# Regulador_RS232.net
KiCad netlist of a schematic drawn in EAGLE
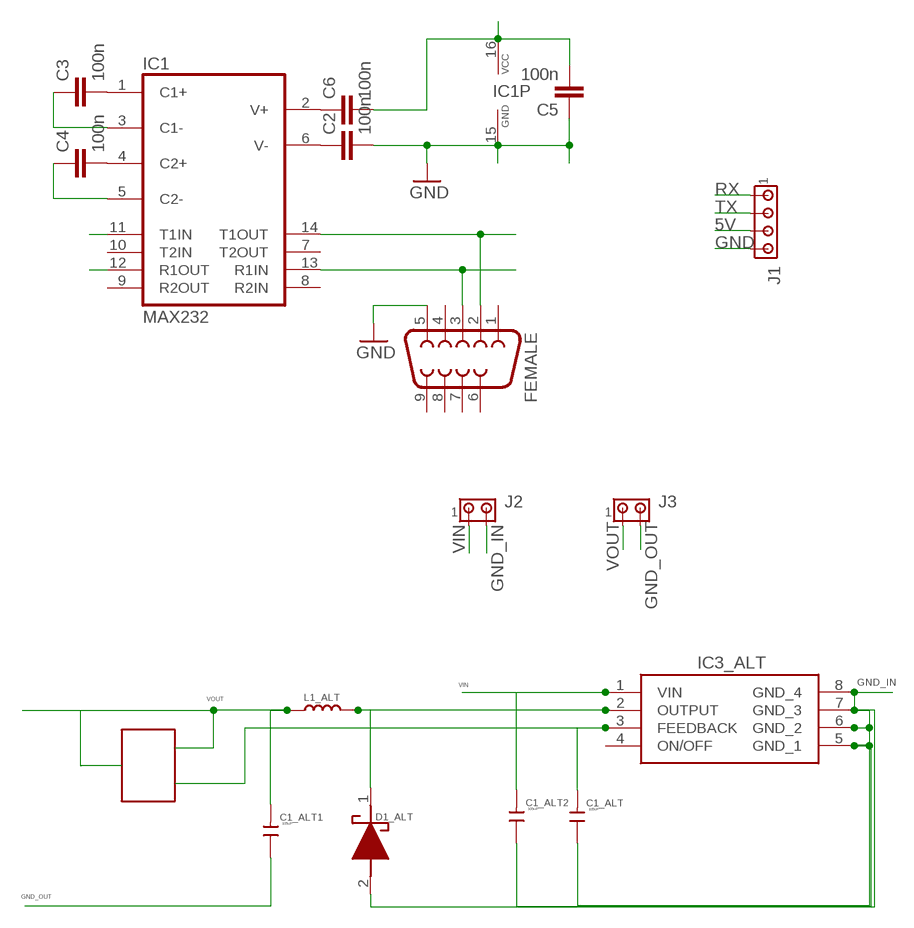
[diagram p0: schematic, sheet 1]

(export (version "E")
  (design (tool "Eeschema 10.0.6"))
  (components
    (comp (ref "C1_ALT")
      (value "105uF")
      (footprint "eagle-import:C0805")
      (libsource (lib "eagle-import") (part "C-0805"))
    )
    (comp (ref "C1_ALT1")
      (value "105uF")
      (footprint "eagle-import:C0805")
      (libsource (lib "eagle-import") (part "C-0805"))
    )
    (comp (ref "C1_ALT2")
      (value "105uF")
      (footprint "eagle-import:C0805")
      (libsource (lib "eagle-import") (part "C-0805"))
    )
    (comp (ref "C2")
      (value "100n")
      (footprint "eagle-import:C0805")
      (libsource (lib "eagle-import") (part "C-EUC0805"))
    )
    (comp (ref "C3")
      (value "100n")
      (footprint "eagle-import:C0805")
      (libsource (lib "eagle-import") (part "C-EUC0805"))
    )
    (comp (ref "C4")
      (value "100n")
      (footprint "eagle-import:C0805")
      (libsource (lib "eagle-import") (part "C-EUC0805"))
    )
    (comp (ref "C5")
      (value "100n")
      (footprint "eagle-import:C0805")
      (libsource (lib "eagle-import") (part "C-EUC0805"))
    )
    (comp (ref "C6")
      (value "100n")
      (footprint "eagle-import:C0805")
      (libsource (lib "eagle-import") (part "C-EUC0805"))
    )
    (comp (ref "D1_ALT")
      (value "1N5819HW1-7-F")
      (footprint "eagle-import:SODFL3518X115N")
      (fields (field (name "MOUSER_PART_NUMBER") "621-1N5819HW1-7-F"))
      (libsource (lib "eagle-import") (part "1N5819HW1-7-F"))
    )
    (comp (ref "FEMALE")
      (value "F09H")
      (footprint "eagle-import:F09H")
      (libsource (lib "eagle-import") (part "F09H"))
    )
    (comp (ref "IC1")
      (value "MAX232")
      (footprint "eagle-import:SO16")
      (libsource (lib "eagle-import") (part "MAX232ECWES"))
    )
    (comp (ref "IC3_ALT")
      (value "XL1509-3.3E1")
      (footprint "eagle-import:SOIC127P600X175-8N")
      (libsource (lib "eagle-import") (part "XL1509-3.3E1"))
    )
    (comp (ref "J1")
      (value "MTA04-156")
      (footprint "eagle-import:1X4MTA")
      (libsource (lib "eagle-import") (part "MTA04-156"))
    )
    (comp (ref "J2")
      (value "MTA02-156")
      (footprint "eagle-import:1X2MTA")
      (libsource (lib "eagle-import") (part "MTA02-156"))
    )
    (comp (ref "J3")
      (value "MTA02-156")
      (footprint "eagle-import:1X2MTA")
      (libsource (lib "eagle-import") (part "MTA02-156"))
    )
    (comp (ref "L1_ALT")
      (value "47uH")
      (footprint "eagle-import:PIO73")
      (libsource (lib "eagle-import") (part "L'PIO73'"))
    )
    (comp (ref "U$1")
      (value "TRIMPOT")
      (footprint "eagle-import:TRIMPOT")
      (libsource (lib "eagle-import") (part "TRIMPOT"))
    )
  )
  (nets
    (net (code "1") (name "/5V") (class "Default")
      (node (ref "C5") (pin "2") (pinfunction "2_2") (pintype "passive"))
      (node (ref "C6") (pin "2") (pinfunction "2_2") (pintype "passive"))
      (node (ref "IC1") (pin "16") (pinfunction "VCC_16") (pintype "power_in"))
      (node (ref "J1") (pin "3") (pinfunction "3_3") (pintype "passive"))
    )
    (net (code "2") (name "/GND_IN") (class "Default")
      (node (ref "C1_ALT") (pin "1") (pinfunction "1_1") (pintype "passive"))
      (node (ref "C1_ALT2") (pin "1") (pinfunction "1_1") (pintype "passive"))
      (node (ref "D1_ALT") (pin "2") (pinfunction "A_2") (pintype "bidirectional"))
      (node (ref "IC3_ALT") (pin "5") (pinfunction "GND_1_5") (pintype "bidirectional"))
      (node (ref "IC3_ALT") (pin "6") (pinfunction "GND_2_6") (pintype "bidirectional"))
      (node (ref "IC3_ALT") (pin "7") (pinfunction "GND_3_7") (pintype "bidirectional"))
      (node (ref "IC3_ALT") (pin "8") (pinfunction "GND_4_8") (pintype "bidirectional"))
      (node (ref "J2") (pin "2") (pinfunction "2_2") (pintype "passive"))
    )
    (net (code "3") (name "/GND_OUT") (class "Default")
      (node (ref "C1_ALT1") (pin "1") (pinfunction "1_1") (pintype "passive"))
      (node (ref "J3") (pin "2") (pinfunction "2_2") (pintype "passive"))
    )
    (net (code "4") (name "/RX") (class "Default")
      (node (ref "IC1") (pin "12") (pinfunction "R1OUT_12") (pintype "output"))
      (node (ref "J1") (pin "1") (pinfunction "1_1") (pintype "passive"))
    )
    (net (code "5") (name "/TX") (class "Default")
      (node (ref "IC1") (pin "11") (pinfunction "T1IN_11") (pintype "input"))
      (node (ref "J1") (pin "2") (pinfunction "2_2") (pintype "passive"))
    )
    (net (code "6") (name "/VIN") (class "Default")
      (node (ref "C1_ALT2") (pin "2") (pinfunction "2_2") (pintype "passive"))
      (node (ref "IC3_ALT") (pin "1") (pinfunction "VIN_1") (pintype "bidirectional"))
      (node (ref "J2") (pin "1") (pinfunction "1_1") (pintype "passive"))
    )
    (net (code "7") (name "/VOUT") (class "Default")
      (node (ref "C1_ALT1") (pin "2") (pinfunction "2_2") (pintype "passive"))
      (node (ref "J3") (pin "1") (pinfunction "1_1") (pintype "passive"))
      (node (ref "L1_ALT") (pin "2") (pinfunction "2_2") (pintype "passive"))
      (node (ref "U$1") (pin "VCC1") (pinfunction "VCC1_VCC1") (pintype "bidirectional"))
      (node (ref "U$1") (pin "VCC2") (pinfunction "VCC2_VCC2") (pintype "bidirectional"))
    )
    (net (code "8") (name "GND") (class "Default")
      (node (ref "C2") (pin "2") (pinfunction "2_2") (pintype "passive"))
      (node (ref "C5") (pin "1") (pinfunction "1_1") (pintype "passive"))
      (node (ref "FEMALE") (pin "5") (pinfunction "5_5") (pintype "passive"))
      (node (ref "IC1") (pin "15") (pinfunction "GND_15") (pintype "power_in"))
      (node (ref "J1") (pin "4") (pinfunction "4_4") (pintype "passive"))
    )
    (net (code "9") (name "Net-(D1_ALT-K)") (class "Default")
      (node (ref "D1_ALT") (pin "1") (pinfunction "K_1") (pintype "bidirectional"))
      (node (ref "IC3_ALT") (pin "2") (pinfunction "OUTPUT_2") (pintype "bidirectional"))
      (node (ref "L1_ALT") (pin "1") (pinfunction "1_1") (pintype "passive"))
    )
    (net (code "10") (name "Net-(IC1A-C1+)") (class "Default")
      (node (ref "C3") (pin "2") (pinfunction "2_2") (pintype "passive"))
      (node (ref "IC1") (pin "1") (pinfunction "C1+_1") (pintype "bidirectional"))
    )
    (net (code "11") (name "Net-(IC1A-C1-)") (class "Default")
      (node (ref "C3") (pin "1") (pinfunction "1_1") (pintype "passive"))
      (node (ref "IC1") (pin "3") (pinfunction "C1-_3") (pintype "bidirectional"))
    )
    (net (code "12") (name "Net-(IC1A-C2+)") (class "Default")
      (node (ref "C4") (pin "2") (pinfunction "2_2") (pintype "passive"))
      (node (ref "IC1") (pin "4") (pinfunction "C2+_4") (pintype "bidirectional"))
    )
    (net (code "13") (name "Net-(IC1A-C2-)") (class "Default")
      (node (ref "C4") (pin "1") (pinfunction "1_1") (pintype "passive"))
      (node (ref "IC1") (pin "5") (pinfunction "C2-_5") (pintype "bidirectional"))
    )
    (net (code "14") (name "Net-(IC1A-R1IN)") (class "Default")
      (node (ref "FEMALE") (pin "3") (pinfunction "3_3") (pintype "passive"))
      (node (ref "IC1") (pin "13") (pinfunction "R1IN_13") (pintype "input"))
    )
    (net (code "15") (name "Net-(IC1A-T1OUT)") (class "Default")
      (node (ref "FEMALE") (pin "2") (pinfunction "2_2") (pintype "passive"))
      (node (ref "IC1") (pin "14") (pinfunction "T1OUT_14") (pintype "output"))
    )
    (net (code "16") (name "Net-(IC1A-V+)") (class "Default")
      (node (ref "C6") (pin "1") (pinfunction "1_1") (pintype "passive"))
      (node (ref "IC1") (pin "2") (pinfunction "V+_2") (pintype "bidirectional"))
    )
    (net (code "17") (name "Net-(IC1A-V-)") (class "Default")
      (node (ref "C2") (pin "1") (pinfunction "1_1") (pintype "passive"))
      (node (ref "IC1") (pin "6") (pinfunction "V-_6") (pintype "bidirectional"))
    )
    (net (code "18") (name "Net-(IC3_ALT-FEEDBACK)") (class "Default")
      (node (ref "C1_ALT") (pin "2") (pinfunction "2_2") (pintype "passive"))
      (node (ref "IC3_ALT") (pin "3") (pinfunction "FEEDBACK_3") (pintype "bidirectional"))
      (node (ref "U$1") (pin "OUT") (pinfunction "OUT_OUT") (pintype "bidirectional"))
    )
    (net (code "19") (name "unconnected-(FEMALE-Pad1)") (class "Default")
      (node (ref "FEMALE") (pin "1") (pinfunction "1_1") (pintype "passive"))
    )
    (net (code "20") (name "unconnected-(FEMALE-Pad4)") (class "Default")
      (node (ref "FEMALE") (pin "4") (pinfunction "4_4") (pintype "passive"))
    )
    (net (code "21") (name "unconnected-(FEMALE-Pad6)") (class "Default")
      (node (ref "FEMALE") (pin "6") (pinfunction "6_6") (pintype "passive"))
    )
    (net (code "22") (name "unconnected-(FEMALE-Pad7)") (class "Default")
      (node (ref "FEMALE") (pin "7") (pinfunction "7_7") (pintype "passive"))
    )
    (net (code "23") (name "unconnected-(FEMALE-Pad8)") (class "Default")
      (node (ref "FEMALE") (pin "8") (pinfunction "8_8") (pintype "passive"))
    )
    (net (code "24") (name "unconnected-(FEMALE-Pad9)") (class "Default")
      (node (ref "FEMALE") (pin "9") (pinfunction "9_9") (pintype "passive"))
    )
    (net (code "25") (name "unconnected-(IC1A-R2IN-Pad8)") (class "Default")
      (node (ref "IC1") (pin "8") (pinfunction "R2IN_8") (pintype "input"))
    )
    (net (code "26") (name "unconnected-(IC1A-R2OUT-Pad9)") (class "Default")
      (node (ref "IC1") (pin "9") (pinfunction "R2OUT_9") (pintype "output"))
    )
    (net (code "27") (name "unconnected-(IC1A-T2IN-Pad10)") (class "Default")
      (node (ref "IC1") (pin "10") (pinfunction "T2IN_10") (pintype "input"))
    )
    (net (code "28") (name "unconnected-(IC1A-T2OUT-Pad7)") (class "Default")
      (node (ref "IC1") (pin "7") (pinfunction "T2OUT_7") (pintype "output"))
    )
    (net (code "29") (name "unconnected-(IC3_ALT-ON{slash}OFF-Pad4)") (class "Default")
      (node (ref "IC3_ALT") (pin "4") (pinfunction "ON/OFF_4") (pintype "bidirectional"))
    )
  )
)
